# 08A-005.net
KiCad netlist of a schematic drawn in EAGLE
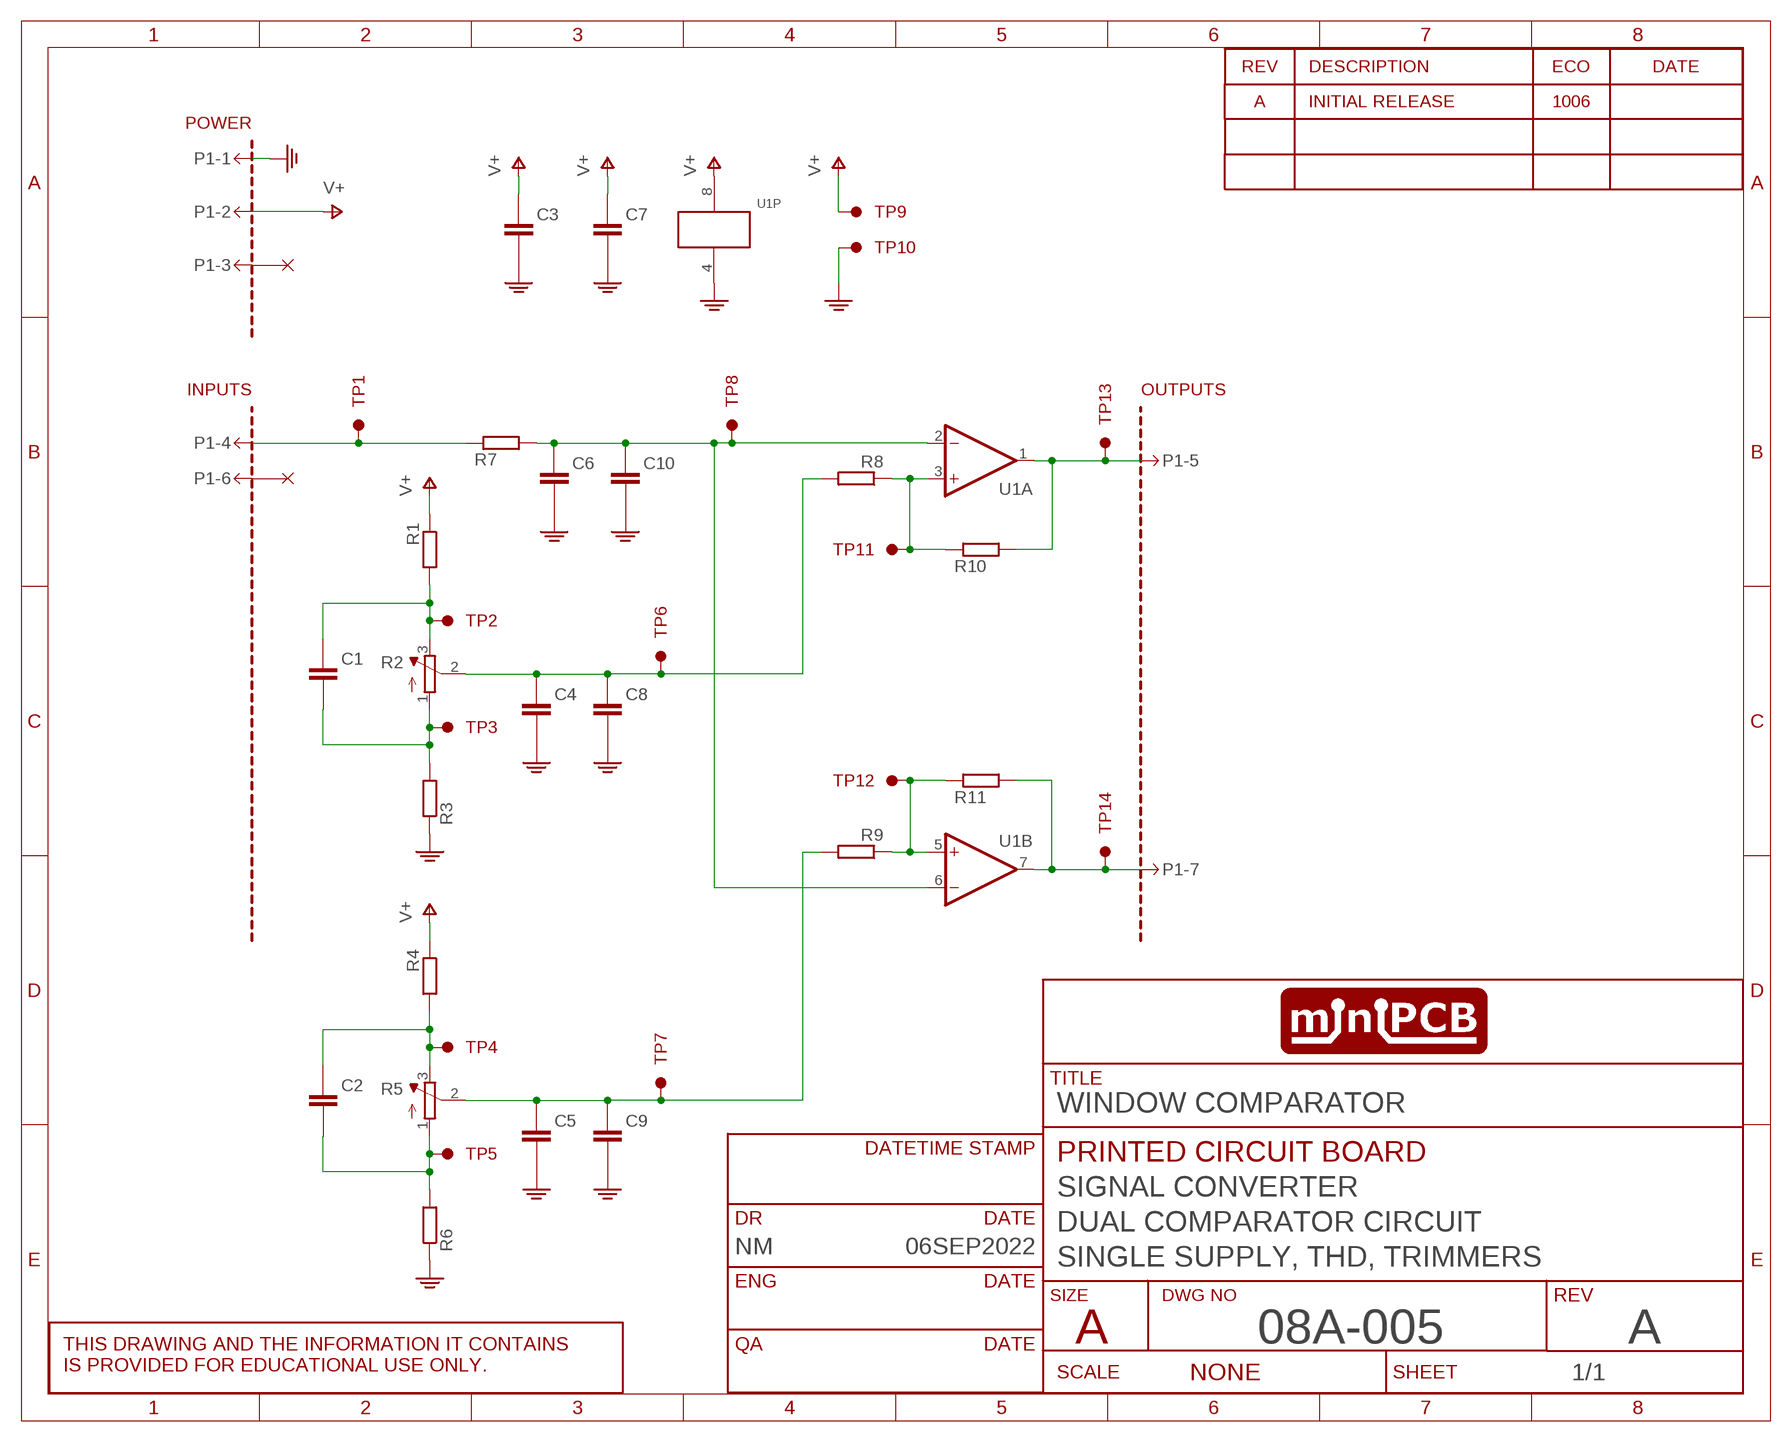
[diagram p0: schematic, sheet 1]

(export (version "E")
  (design (tool "Eeschema 10.0.6"))
  (components
    (comp (ref "C1")
      (value "CAPACITORTHD")
      (footprint "eagle-import:C050-024X044")
      (libsource (lib "eagle-import") (part "CAPACITORTHD"))
    )
    (comp (ref "C2")
      (value "CAPACITORTHD")
      (footprint "eagle-import:C050-024X044")
      (libsource (lib "eagle-import") (part "CAPACITORTHD"))
    )
    (comp (ref "C3")
      (value "CAPACITORTHD")
      (footprint "eagle-import:C050-024X044")
      (libsource (lib "eagle-import") (part "CAPACITORTHD"))
    )
    (comp (ref "C4")
      (value "CAPACITORTHD")
      (footprint "eagle-import:C050-024X044")
      (libsource (lib "eagle-import") (part "CAPACITORTHD"))
    )
    (comp (ref "C5")
      (value "CAPACITORTHD")
      (footprint "eagle-import:C050-024X044")
      (libsource (lib "eagle-import") (part "CAPACITORTHD"))
    )
    (comp (ref "C6")
      (value "CAPACITORTHD")
      (footprint "eagle-import:C050-024X044")
      (libsource (lib "eagle-import") (part "CAPACITORTHD"))
    )
    (comp (ref "C7")
      (value "CAPACITORTHD")
      (footprint "eagle-import:C050-024X044")
      (libsource (lib "eagle-import") (part "CAPACITORTHD"))
    )
    (comp (ref "C8")
      (value "CAPACITORTHD")
      (footprint "eagle-import:C050-024X044")
      (libsource (lib "eagle-import") (part "CAPACITORTHD"))
    )
    (comp (ref "C9")
      (value "CAPACITORTHD")
      (footprint "eagle-import:C050-024X044")
      (libsource (lib "eagle-import") (part "CAPACITORTHD"))
    )
    (comp (ref "C10")
      (value "CAPACITORTHD")
      (footprint "eagle-import:C050-024X044")
      (libsource (lib "eagle-import") (part "CAPACITORTHD"))
    )
    (comp (ref "P1-")
      (value "MINIPCB_7P50")
      (footprint "eagle-import:MINIPCB_7P_50X50")
      (fields (field (name "PART_NUMBER") "X08A-005-A"))
      (libsource (lib "eagle-import") (part "MINIPCB_7P50"))
    )
    (comp (ref "R1")
      (value "RESISTOR10MM")
      (footprint "eagle-import:0207_10")
      (libsource (lib "eagle-import") (part "RESISTOR10MM"))
    )
    (comp (ref "R2")
      (value "TRIMPOT0.100THD")
      (footprint "eagle-import:TRIM_0100")
      (libsource (lib "eagle-import") (part "TRIMPOT0.100THD"))
    )
    (comp (ref "R3")
      (value "RESISTOR10MM")
      (footprint "eagle-import:0207_10")
      (libsource (lib "eagle-import") (part "RESISTOR10MM"))
    )
    (comp (ref "R4")
      (value "RESISTOR10MM")
      (footprint "eagle-import:0207_10")
      (libsource (lib "eagle-import") (part "RESISTOR10MM"))
    )
    (comp (ref "R5")
      (value "TRIMPOT0.100THD")
      (footprint "eagle-import:TRIM_0100")
      (libsource (lib "eagle-import") (part "TRIMPOT0.100THD"))
    )
    (comp (ref "R6")
      (value "RESISTOR10MM")
      (footprint "eagle-import:0207_10")
      (libsource (lib "eagle-import") (part "RESISTOR10MM"))
    )
    (comp (ref "R7")
      (value "RESISTOR10MM")
      (footprint "eagle-import:0207_10")
      (libsource (lib "eagle-import") (part "RESISTOR10MM"))
    )
    (comp (ref "R8")
      (value "RESISTOR10MM")
      (footprint "eagle-import:0207_10")
      (libsource (lib "eagle-import") (part "RESISTOR10MM"))
    )
    (comp (ref "R9")
      (value "RESISTOR10MM")
      (footprint "eagle-import:0207_10")
      (libsource (lib "eagle-import") (part "RESISTOR10MM"))
    )
    (comp (ref "R10")
      (value "RESISTOR10MM")
      (footprint "eagle-import:0207_10")
      (libsource (lib "eagle-import") (part "RESISTOR10MM"))
    )
    (comp (ref "R11")
      (value "RESISTOR10MM")
      (footprint "eagle-import:0207_10")
      (libsource (lib "eagle-import") (part "RESISTOR10MM"))
    )
    (comp (ref "TP1")
      (value "TESTPOINTKE5000-SMTEXT")
      (footprint "eagle-import:PINS_1_TESTPOINT_KE5000_NOTEXT")
      (libsource (lib "eagle-import") (part "TESTPOINTKE5000-SMTEXT"))
    )
    (comp (ref "TP2")
      (value "TESTPOINTKE5000-SMTEXT")
      (footprint "eagle-import:PINS_1_TESTPOINT_KE5000_NOTEXT")
      (libsource (lib "eagle-import") (part "TESTPOINTKE5000-SMTEXT"))
    )
    (comp (ref "TP3")
      (value "TESTPOINTKE5000-SMTEXT")
      (footprint "eagle-import:PINS_1_TESTPOINT_KE5000_NOTEXT")
      (libsource (lib "eagle-import") (part "TESTPOINTKE5000-SMTEXT"))
    )
    (comp (ref "TP4")
      (value "TESTPOINTKE5000-SMTEXT")
      (footprint "eagle-import:PINS_1_TESTPOINT_KE5000_NOTEXT")
      (libsource (lib "eagle-import") (part "TESTPOINTKE5000-SMTEXT"))
    )
    (comp (ref "TP5")
      (value "TESTPOINTKE5000-SMTEXT")
      (footprint "eagle-import:PINS_1_TESTPOINT_KE5000_NOTEXT")
      (libsource (lib "eagle-import") (part "TESTPOINTKE5000-SMTEXT"))
    )
    (comp (ref "TP6")
      (value "TESTPOINTKE5000-SMTEXT")
      (footprint "eagle-import:PINS_1_TESTPOINT_KE5000_NOTEXT")
      (libsource (lib "eagle-import") (part "TESTPOINTKE5000-SMTEXT"))
    )
    (comp (ref "TP7")
      (value "TESTPOINTKE5000-SMTEXT")
      (footprint "eagle-import:PINS_1_TESTPOINT_KE5000_NOTEXT")
      (libsource (lib "eagle-import") (part "TESTPOINTKE5000-SMTEXT"))
    )
    (comp (ref "TP8")
      (value "TESTPOINTKE5000-SMTEXT")
      (footprint "eagle-import:PINS_1_TESTPOINT_KE5000_NOTEXT")
      (libsource (lib "eagle-import") (part "TESTPOINTKE5000-SMTEXT"))
    )
    (comp (ref "TP9")
      (value "TESTPOINTKE5000-SMTEXT")
      (footprint "eagle-import:PINS_1_TESTPOINT_KE5000_NOTEXT")
      (libsource (lib "eagle-import") (part "TESTPOINTKE5000-SMTEXT"))
    )
    (comp (ref "TP10")
      (value "TESTPOINTKE5000-SMTEXT")
      (footprint "eagle-import:PINS_1_TESTPOINT_KE5000_NOTEXT")
      (libsource (lib "eagle-import") (part "TESTPOINTKE5000-SMTEXT"))
    )
    (comp (ref "TP11")
      (value "TESTPOINTKE5000-SMTEXT")
      (footprint "eagle-import:PINS_1_TESTPOINT_KE5000_NOTEXT")
      (libsource (lib "eagle-import") (part "TESTPOINTKE5000-SMTEXT"))
    )
    (comp (ref "TP12")
      (value "TESTPOINTKE5000-SMTEXT")
      (footprint "eagle-import:PINS_1_TESTPOINT_KE5000_NOTEXT")
      (libsource (lib "eagle-import") (part "TESTPOINTKE5000-SMTEXT"))
    )
    (comp (ref "TP13")
      (value "TESTPOINTKE5000-SMTEXT")
      (footprint "eagle-import:PINS_1_TESTPOINT_KE5000_NOTEXT")
      (libsource (lib "eagle-import") (part "TESTPOINTKE5000-SMTEXT"))
    )
    (comp (ref "TP14")
      (value "TESTPOINTKE5000-SMTEXT")
      (footprint "eagle-import:PINS_1_TESTPOINT_KE5000_NOTEXT")
      (libsource (lib "eagle-import") (part "TESTPOINTKE5000-SMTEXT"))
    )
    (comp (ref "U1")
      (value "OPAMP_DUALTHD")
      (footprint "eagle-import:DIL08")
      (libsource (lib "eagle-import") (part "OPAMP_DUALTHD"))
    )
  )
  (nets
    (net (code "1") (name "GND") (class "Default")
      (node (ref "C10") (pin "2") (pinfunction "-_2") (pintype "passive"))
      (node (ref "C3") (pin "2") (pinfunction "-_2") (pintype "passive"))
      (node (ref "C4") (pin "2") (pinfunction "-_2") (pintype "passive"))
      (node (ref "C5") (pin "2") (pinfunction "-_2") (pintype "passive"))
      (node (ref "C6") (pin "2") (pinfunction "-_2") (pintype "passive"))
      (node (ref "C7") (pin "2") (pinfunction "-_2") (pintype "passive"))
      (node (ref "C8") (pin "2") (pinfunction "-_2") (pintype "passive"))
      (node (ref "C9") (pin "2") (pinfunction "-_2") (pintype "passive"))
      (node (ref "P1-") (pin "1") (pinfunction "1_1") (pintype "bidirectional"))
      (node (ref "R3") (pin "1") (pinfunction "1_1") (pintype "passive"))
      (node (ref "R6") (pin "1") (pinfunction "1_1") (pintype "passive"))
      (node (ref "TP10") (pin "1") (pinfunction "1_1") (pintype "bidirectional"))
      (node (ref "U1") (pin "4") (pinfunction "V-_4") (pintype "power_in"))
    )
    (net (code "2") (name "Net-(C1-+)") (class "Default")
      (node (ref "C1") (pin "1") (pinfunction "+_1") (pintype "passive"))
      (node (ref "R1") (pin "2") (pinfunction "2_2") (pintype "passive"))
      (node (ref "R2") (pin "3") (pinfunction "E_3") (pintype "passive"))
      (node (ref "TP2") (pin "1") (pinfunction "1_1") (pintype "bidirectional"))
    )
    (net (code "3") (name "Net-(C1--)") (class "Default")
      (node (ref "C1") (pin "2") (pinfunction "-_2") (pintype "passive"))
      (node (ref "R2") (pin "1") (pinfunction "A_1") (pintype "passive"))
      (node (ref "R3") (pin "2") (pinfunction "2_2") (pintype "passive"))
      (node (ref "TP3") (pin "1") (pinfunction "1_1") (pintype "bidirectional"))
    )
    (net (code "4") (name "Net-(C2-+)") (class "Default")
      (node (ref "C2") (pin "1") (pinfunction "+_1") (pintype "passive"))
      (node (ref "R4") (pin "2") (pinfunction "2_2") (pintype "passive"))
      (node (ref "R5") (pin "3") (pinfunction "E_3") (pintype "passive"))
      (node (ref "TP4") (pin "1") (pinfunction "1_1") (pintype "bidirectional"))
    )
    (net (code "5") (name "Net-(C2--)") (class "Default")
      (node (ref "C2") (pin "2") (pinfunction "-_2") (pintype "passive"))
      (node (ref "R5") (pin "1") (pinfunction "A_1") (pintype "passive"))
      (node (ref "R6") (pin "2") (pinfunction "2_2") (pintype "passive"))
      (node (ref "TP5") (pin "1") (pinfunction "1_1") (pintype "bidirectional"))
    )
    (net (code "6") (name "Net-(C4-+)") (class "Default")
      (node (ref "C4") (pin "1") (pinfunction "+_1") (pintype "passive"))
      (node (ref "C8") (pin "1") (pinfunction "+_1") (pintype "passive"))
      (node (ref "R2") (pin "2") (pinfunction "S_2") (pintype "passive"))
      (node (ref "R8") (pin "2") (pinfunction "2_2") (pintype "passive"))
      (node (ref "TP6") (pin "1") (pinfunction "1_1") (pintype "bidirectional"))
    )
    (net (code "7") (name "Net-(C5-+)") (class "Default")
      (node (ref "C5") (pin "1") (pinfunction "+_1") (pintype "passive"))
      (node (ref "C9") (pin "1") (pinfunction "+_1") (pintype "passive"))
      (node (ref "R5") (pin "2") (pinfunction "S_2") (pintype "passive"))
      (node (ref "R9") (pin "2") (pinfunction "2_2") (pintype "passive"))
      (node (ref "TP7") (pin "1") (pinfunction "1_1") (pintype "bidirectional"))
    )
    (net (code "8") (name "Net-(C10-+)") (class "Default")
      (node (ref "C10") (pin "1") (pinfunction "+_1") (pintype "passive"))
      (node (ref "C6") (pin "1") (pinfunction "+_1") (pintype "passive"))
      (node (ref "R7") (pin "2") (pinfunction "2_2") (pintype "passive"))
      (node (ref "TP8") (pin "1") (pinfunction "1_1") (pintype "bidirectional"))
      (node (ref "U1") (pin "2") (pinfunction "-IN_2") (pintype "input"))
      (node (ref "U1") (pin "6") (pinfunction "-IN_6") (pintype "input"))
    )
    (net (code "9") (name "Net-(P1-D-1)") (class "Default")
      (node (ref "P1-") (pin "4") (pinfunction "1_4") (pintype "bidirectional"))
      (node (ref "R7") (pin "1") (pinfunction "1_1") (pintype "passive"))
      (node (ref "TP1") (pin "1") (pinfunction "1_1") (pintype "bidirectional"))
    )
    (net (code "10") (name "Net-(P1-E-1)") (class "Default")
      (node (ref "P1-") (pin "5") (pinfunction "1_5") (pintype "bidirectional"))
      (node (ref "R10") (pin "2") (pinfunction "2_2") (pintype "passive"))
      (node (ref "TP13") (pin "1") (pinfunction "1_1") (pintype "bidirectional"))
      (node (ref "U1") (pin "1") (pinfunction "OUT_1") (pintype "output"))
    )
    (net (code "11") (name "Net-(P1-G-1)") (class "Default")
      (node (ref "P1-") (pin "7") (pinfunction "1_7") (pintype "bidirectional"))
      (node (ref "R11") (pin "2") (pinfunction "2_2") (pintype "passive"))
      (node (ref "TP14") (pin "1") (pinfunction "1_1") (pintype "bidirectional"))
      (node (ref "U1") (pin "7") (pinfunction "OUT_7") (pintype "output"))
    )
    (net (code "12") (name "Net-(U1A-+IN)") (class "Default")
      (node (ref "R10") (pin "1") (pinfunction "1_1") (pintype "passive"))
      (node (ref "R8") (pin "1") (pinfunction "1_1") (pintype "passive"))
      (node (ref "TP11") (pin "1") (pinfunction "1_1") (pintype "bidirectional"))
      (node (ref "U1") (pin "3") (pinfunction "+IN_3") (pintype "input"))
    )
    (net (code "13") (name "Net-(U1B-+IN)") (class "Default")
      (node (ref "R11") (pin "1") (pinfunction "1_1") (pintype "passive"))
      (node (ref "R9") (pin "1") (pinfunction "1_1") (pintype "passive"))
      (node (ref "TP12") (pin "1") (pinfunction "1_1") (pintype "bidirectional"))
      (node (ref "U1") (pin "5") (pinfunction "+IN_5") (pintype "input"))
    )
    (net (code "14") (name "V+") (class "Default")
      (node (ref "C3") (pin "1") (pinfunction "+_1") (pintype "passive"))
      (node (ref "C7") (pin "1") (pinfunction "+_1") (pintype "passive"))
      (node (ref "P1-") (pin "2") (pinfunction "1_2") (pintype "bidirectional"))
      (node (ref "R1") (pin "1") (pinfunction "1_1") (pintype "passive"))
      (node (ref "R4") (pin "1") (pinfunction "1_1") (pintype "passive"))
      (node (ref "TP9") (pin "1") (pinfunction "1_1") (pintype "bidirectional"))
      (node (ref "U1") (pin "8") (pinfunction "V+_8") (pintype "power_in"))
    )
    (net (code "15") (name "unconnected-(P1-C-1-Pad3)") (class "Default")
      (node (ref "P1-") (pin "3") (pinfunction "1_3") (pintype "bidirectional"))
    )
    (net (code "16") (name "unconnected-(P1-F-1-Pad6)") (class "Default")
      (node (ref "P1-") (pin "6") (pinfunction "1_6") (pintype "bidirectional"))
    )
  )
)
